# FAL6567.net
KiCad netlist of a schematic drawn in EAGLE
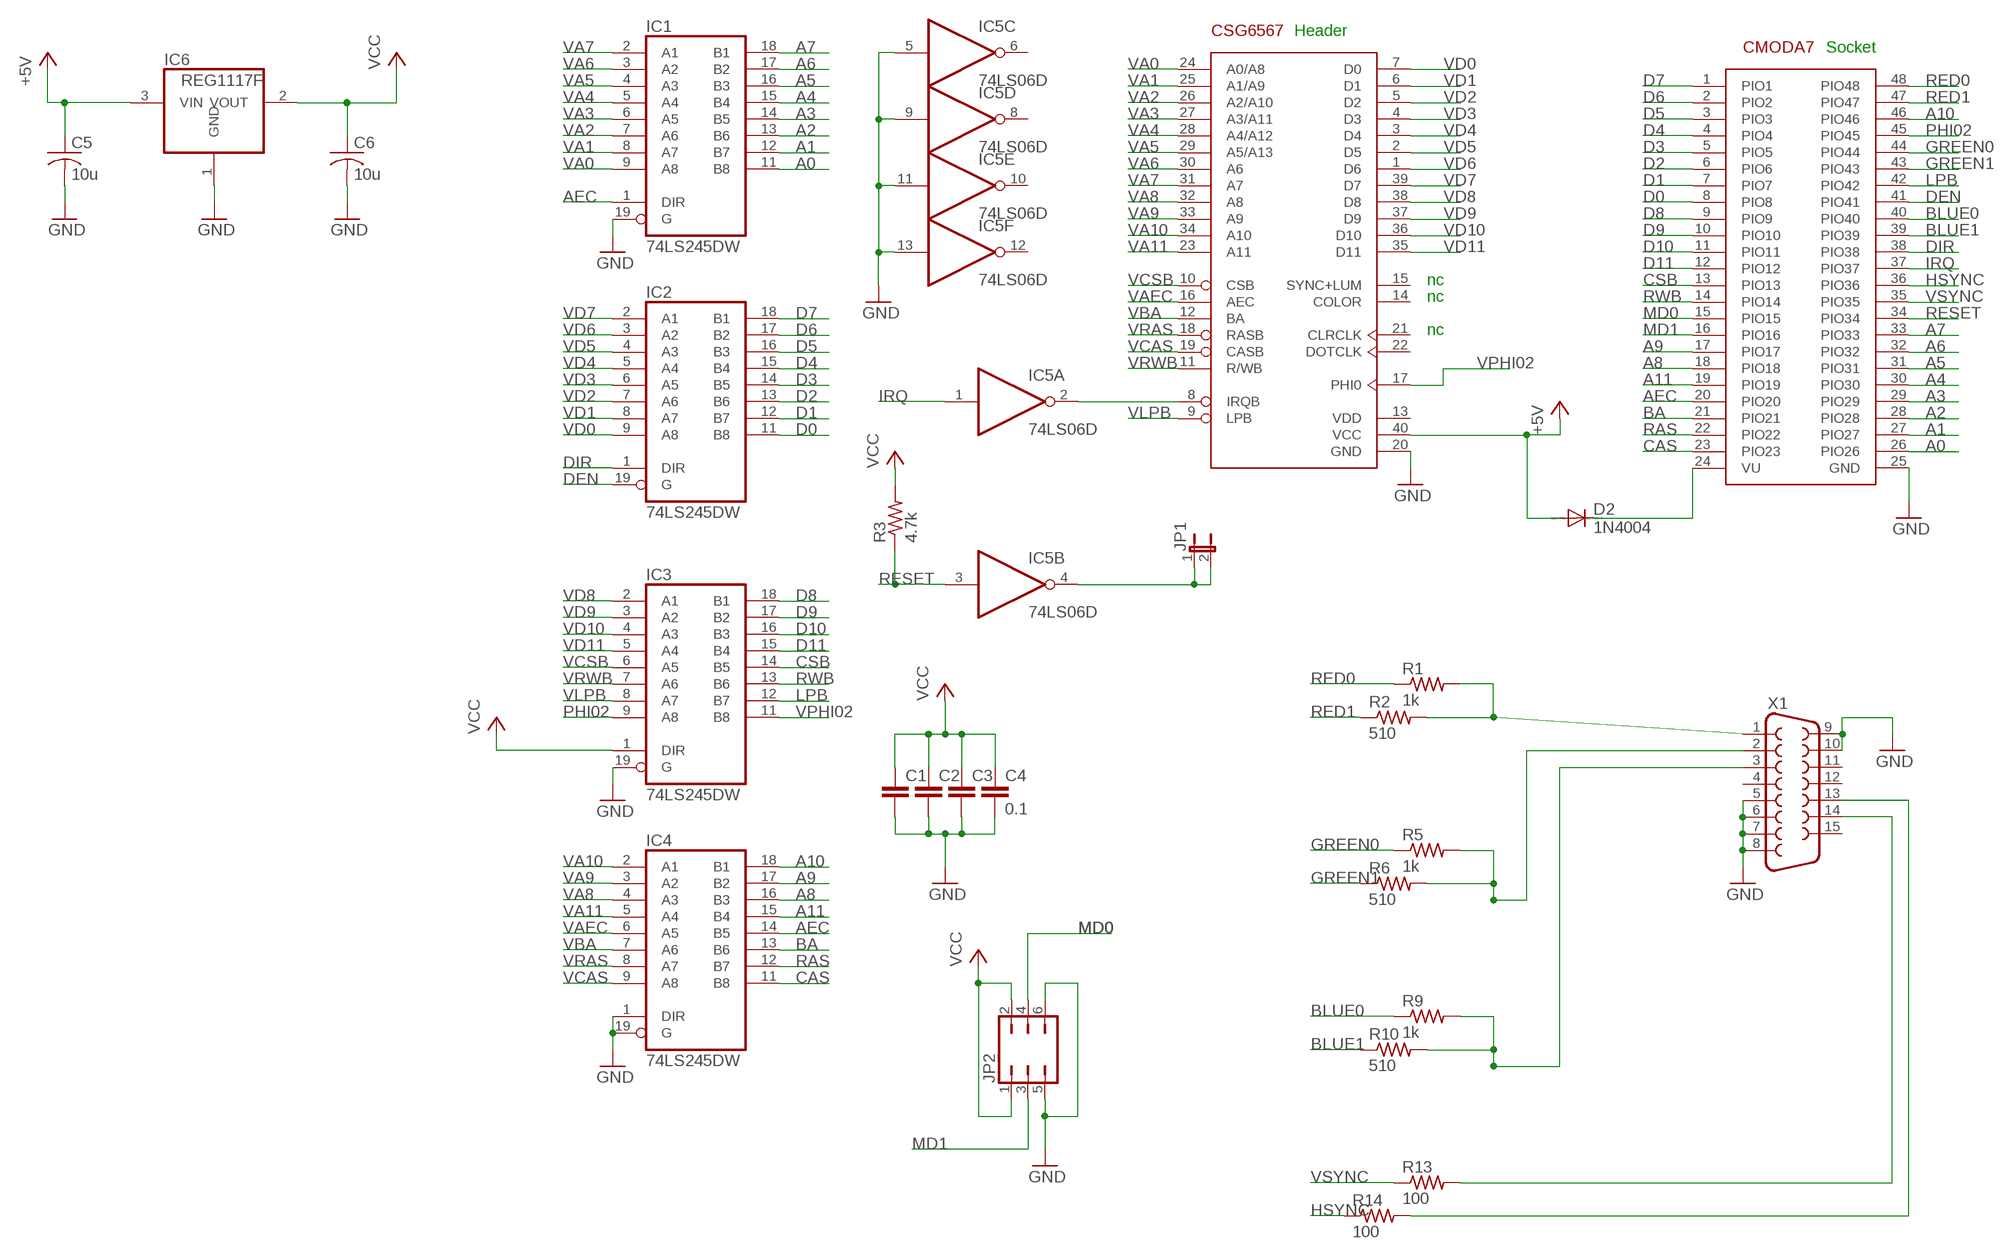
[diagram p0: schematic, sheet 1]

(export (version "E")
  (design (tool "Eeschema 10.0.6"))
  (components
    (comp (ref "C1")
      (value "C-EU050-024X044")
      (footprint "eagle-import:C050-024X044")
      (libsource (lib "eagle-import") (part "C-EU050-024X044"))
    )
    (comp (ref "C2")
      (value "C-EU050-024X044")
      (footprint "eagle-import:C050-024X044")
      (libsource (lib "eagle-import") (part "C-EU050-024X044"))
    )
    (comp (ref "C3")
      (value "C-EU050-024X044")
      (footprint "eagle-import:C050-024X044")
      (libsource (lib "eagle-import") (part "C-EU050-024X044"))
    )
    (comp (ref "C4")
      (value "0.1")
      (footprint "eagle-import:C050-024X044")
      (libsource (lib "eagle-import") (part "C-EU050-024X044"))
    )
    (comp (ref "C5")
      (value "10u")
      (footprint "eagle-import:C1206")
      (libsource (lib "eagle-import") (part "C-USC1206"))
    )
    (comp (ref "C6")
      (value "10u")
      (footprint "eagle-import:C1206")
      (libsource (lib "eagle-import") (part "C-USC1206"))
    )
    (comp (ref "D2")
      (value "1N4004")
      (footprint "eagle-import:DO41-10")
      (libsource (lib "eagle-import") (part "1N4004"))
    )
    (comp (ref "IC1")
      (value "74LS245DW")
      (footprint "eagle-import:SO20W")
      (libsource (lib "eagle-import") (part "74245DWLS"))
    )
    (comp (ref "IC2")
      (value "74LS245DW")
      (footprint "eagle-import:SO20W")
      (libsource (lib "eagle-import") (part "74245DWLS"))
    )
    (comp (ref "IC3")
      (value "74LS245DW")
      (footprint "eagle-import:SO20W")
      (libsource (lib "eagle-import") (part "74245DWLS"))
    )
    (comp (ref "IC4")
      (value "74LS245DW")
      (footprint "eagle-import:SO20W")
      (libsource (lib "eagle-import") (part "74245DWLS"))
    )
    (comp (ref "IC5")
      (value "74LS06D")
      (footprint "eagle-import:SO14")
      (libsource (lib "eagle-import") (part "7406DLS"))
    )
    (comp (ref "IC6")
      (value "REG1117F")
      (footprint "eagle-import:DD-3")
      (fields (field (name "MF") "TEXAS INSTRUMENTS") (field (name "MPN") "REG1117FAKTTT"))
      (libsource (lib "eagle-import") (part "REG1117F"))
    )
    (comp (ref "JP1")
      (value "JP1E")
      (footprint "eagle-import:JP1")
      (libsource (lib "eagle-import") (part "JP1E"))
    )
    (comp (ref "JP2")
      (value "JP3Q")
      (footprint "eagle-import:JP3Q")
      (libsource (lib "eagle-import") (part "JP3Q"))
    )
    (comp (ref "R1")
      (value "1k")
      (footprint "eagle-import:0204_7")
      (libsource (lib "eagle-import") (part "R-US_0204/7"))
    )
    (comp (ref "R2")
      (value "510")
      (footprint "eagle-import:0204_7")
      (libsource (lib "eagle-import") (part "R-US_0204/7"))
    )
    (comp (ref "R3")
      (value "4.7k")
      (footprint "eagle-import:0204_7")
      (libsource (lib "eagle-import") (part "R-US_0204/7"))
    )
    (comp (ref "R5")
      (value "1k")
      (footprint "eagle-import:0204_7")
      (libsource (lib "eagle-import") (part "R-US_0204/7"))
    )
    (comp (ref "R6")
      (value "510")
      (footprint "eagle-import:0204_7")
      (libsource (lib "eagle-import") (part "R-US_0204/7"))
    )
    (comp (ref "R9")
      (value "1k")
      (footprint "eagle-import:0204_7")
      (libsource (lib "eagle-import") (part "R-US_0204/7"))
    )
    (comp (ref "R10")
      (value "510")
      (footprint "eagle-import:0204_7")
      (libsource (lib "eagle-import") (part "R-US_0204/7"))
    )
    (comp (ref "R13")
      (value "100")
      (footprint "eagle-import:0204_7")
      (libsource (lib "eagle-import") (part "R-US_0204/7"))
    )
    (comp (ref "R14")
      (value "100")
      (footprint "eagle-import:0204_7")
      (libsource (lib "eagle-import") (part "R-US_0204/7"))
    )
    (comp (ref "U$1")
      (value "CSG6567")
      (footprint "eagle-import:DIP-40")
      (libsource (lib "eagle-import") (part "CSG6567"))
    )
    (comp (ref "U$2")
      (value "CMODA7")
      (footprint "eagle-import:DIL48")
      (libsource (lib "eagle-import") (part "CMODA7"))
    )
    (comp (ref "X1")
      (value "F15HDV")
      (footprint "eagle-import:HDF15V")
      (libsource (lib "eagle-import") (part "F15HDV"))
    )
  )
  (nets
    (net (code "1") (name "+5V") (class "Default")
      (node (ref "C5") (pin "1") (pinfunction "1_1") (pintype "passive"))
      (node (ref "D2") (pin "A") (pinfunction "A_A") (pintype "passive"))
      (node (ref "IC6") (pin "3") (pinfunction "VIN_3") (pintype "input"))
      (node (ref "U$1") (pin "40") (pinfunction "VCC_40") (pintype "power_in"))
    )
    (net (code "2") (name "/A0") (class "Default")
      (node (ref "IC1") (pin "11") (pinfunction "B8_11") (pintype "bidirectional"))
      (node (ref "U$2") (pin "26") (pinfunction "PIO26_26") (pintype "bidirectional"))
    )
    (net (code "3") (name "/A1") (class "Default")
      (node (ref "IC1") (pin "12") (pinfunction "B7_12") (pintype "bidirectional"))
      (node (ref "U$2") (pin "27") (pinfunction "PIO27_27") (pintype "bidirectional"))
    )
    (net (code "4") (name "/A2") (class "Default")
      (node (ref "IC1") (pin "13") (pinfunction "B6_13") (pintype "bidirectional"))
      (node (ref "U$2") (pin "28") (pinfunction "PIO28_28") (pintype "bidirectional"))
    )
    (net (code "5") (name "/A3") (class "Default")
      (node (ref "IC1") (pin "14") (pinfunction "B5_14") (pintype "bidirectional"))
      (node (ref "U$2") (pin "29") (pinfunction "PIO29_29") (pintype "bidirectional"))
    )
    (net (code "6") (name "/A4") (class "Default")
      (node (ref "IC1") (pin "15") (pinfunction "B4_15") (pintype "bidirectional"))
      (node (ref "U$2") (pin "30") (pinfunction "PIO30_30") (pintype "bidirectional"))
    )
    (net (code "7") (name "/A5") (class "Default")
      (node (ref "IC1") (pin "16") (pinfunction "B3_16") (pintype "bidirectional"))
      (node (ref "U$2") (pin "31") (pinfunction "PIO31_31") (pintype "bidirectional"))
    )
    (net (code "8") (name "/A6") (class "Default")
      (node (ref "IC1") (pin "17") (pinfunction "B2_17") (pintype "bidirectional"))
      (node (ref "U$2") (pin "32") (pinfunction "PIO32_32") (pintype "bidirectional"))
    )
    (net (code "9") (name "/A7") (class "Default")
      (node (ref "IC1") (pin "18") (pinfunction "B1_18") (pintype "bidirectional"))
      (node (ref "U$2") (pin "33") (pinfunction "PIO33_33") (pintype "bidirectional"))
    )
    (net (code "10") (name "/A8") (class "Default")
      (node (ref "IC4") (pin "16") (pinfunction "B3_16") (pintype "bidirectional"))
      (node (ref "U$2") (pin "18") (pinfunction "PIO18_18") (pintype "bidirectional"))
    )
    (net (code "11") (name "/A9") (class "Default")
      (node (ref "IC4") (pin "17") (pinfunction "B2_17") (pintype "bidirectional"))
      (node (ref "U$2") (pin "17") (pinfunction "PIO17_17") (pintype "bidirectional"))
    )
    (net (code "12") (name "/A10") (class "Default")
      (node (ref "IC4") (pin "18") (pinfunction "B1_18") (pintype "bidirectional"))
      (node (ref "U$2") (pin "46") (pinfunction "PIO46_46") (pintype "bidirectional"))
    )
    (net (code "13") (name "/A11") (class "Default")
      (node (ref "IC4") (pin "15") (pinfunction "B4_15") (pintype "bidirectional"))
      (node (ref "U$2") (pin "19") (pinfunction "PIO19_19") (pintype "bidirectional"))
    )
    (net (code "14") (name "/AEC") (class "Default")
      (node (ref "IC1") (pin "1") (pinfunction "DIR_1") (pintype "input"))
      (node (ref "IC4") (pin "14") (pinfunction "B5_14") (pintype "bidirectional"))
      (node (ref "U$2") (pin "20") (pinfunction "PIO20_20") (pintype "bidirectional"))
    )
    (net (code "15") (name "/BA") (class "Default")
      (node (ref "IC4") (pin "13") (pinfunction "B6_13") (pintype "bidirectional"))
      (node (ref "U$2") (pin "21") (pinfunction "PIO21_21") (pintype "bidirectional"))
    )
    (net (code "16") (name "/BLUE0") (class "Default")
      (node (ref "R9") (pin "1") (pinfunction "1_1") (pintype "passive"))
      (node (ref "U$2") (pin "40") (pinfunction "PIO40_40") (pintype "bidirectional"))
    )
    (net (code "17") (name "/BLUE1") (class "Default")
      (node (ref "R10") (pin "1") (pinfunction "1_1") (pintype "passive"))
      (node (ref "U$2") (pin "39") (pinfunction "PIO39_39") (pintype "bidirectional"))
    )
    (net (code "18") (name "/CAS") (class "Default")
      (node (ref "IC4") (pin "11") (pinfunction "B8_11") (pintype "bidirectional"))
      (node (ref "U$2") (pin "23") (pinfunction "PIO23_23") (pintype "bidirectional"))
    )
    (net (code "19") (name "/CSB") (class "Default")
      (node (ref "IC3") (pin "14") (pinfunction "B5_14") (pintype "bidirectional"))
      (node (ref "U$2") (pin "13") (pinfunction "PIO13_13") (pintype "bidirectional"))
    )
    (net (code "20") (name "/D0") (class "Default")
      (node (ref "IC2") (pin "11") (pinfunction "B8_11") (pintype "bidirectional"))
      (node (ref "U$2") (pin "8") (pinfunction "PIO8_8") (pintype "bidirectional"))
    )
    (net (code "21") (name "/D1") (class "Default")
      (node (ref "IC2") (pin "12") (pinfunction "B7_12") (pintype "bidirectional"))
      (node (ref "U$2") (pin "7") (pinfunction "PIO7_7") (pintype "bidirectional"))
    )
    (net (code "22") (name "/D2") (class "Default")
      (node (ref "IC2") (pin "13") (pinfunction "B6_13") (pintype "bidirectional"))
      (node (ref "U$2") (pin "6") (pinfunction "PIO6_6") (pintype "bidirectional"))
    )
    (net (code "23") (name "/D3") (class "Default")
      (node (ref "IC2") (pin "14") (pinfunction "B5_14") (pintype "bidirectional"))
      (node (ref "U$2") (pin "5") (pinfunction "PIO5_5") (pintype "bidirectional"))
    )
    (net (code "24") (name "/D4") (class "Default")
      (node (ref "IC2") (pin "15") (pinfunction "B4_15") (pintype "bidirectional"))
      (node (ref "U$2") (pin "4") (pinfunction "PIO4_4") (pintype "bidirectional"))
    )
    (net (code "25") (name "/D5") (class "Default")
      (node (ref "IC2") (pin "16") (pinfunction "B3_16") (pintype "bidirectional"))
      (node (ref "U$2") (pin "3") (pinfunction "PIO3_3") (pintype "bidirectional"))
    )
    (net (code "26") (name "/D6") (class "Default")
      (node (ref "IC2") (pin "17") (pinfunction "B2_17") (pintype "bidirectional"))
      (node (ref "U$2") (pin "2") (pinfunction "PIO2_2") (pintype "bidirectional"))
    )
    (net (code "27") (name "/D7") (class "Default")
      (node (ref "IC2") (pin "18") (pinfunction "B1_18") (pintype "bidirectional"))
      (node (ref "U$2") (pin "1") (pinfunction "PIO1_1") (pintype "bidirectional"))
    )
    (net (code "28") (name "/D8") (class "Default")
      (node (ref "IC3") (pin "18") (pinfunction "B1_18") (pintype "bidirectional"))
      (node (ref "U$2") (pin "9") (pinfunction "PIO9_9") (pintype "bidirectional"))
    )
    (net (code "29") (name "/D9") (class "Default")
      (node (ref "IC3") (pin "17") (pinfunction "B2_17") (pintype "bidirectional"))
      (node (ref "U$2") (pin "10") (pinfunction "PIO10_10") (pintype "bidirectional"))
    )
    (net (code "30") (name "/D10") (class "Default")
      (node (ref "IC3") (pin "16") (pinfunction "B3_16") (pintype "bidirectional"))
      (node (ref "U$2") (pin "11") (pinfunction "PIO11_11") (pintype "bidirectional"))
    )
    (net (code "31") (name "/D11") (class "Default")
      (node (ref "IC3") (pin "15") (pinfunction "B4_15") (pintype "bidirectional"))
      (node (ref "U$2") (pin "12") (pinfunction "PIO12_12") (pintype "bidirectional"))
    )
    (net (code "32") (name "/DEN") (class "Default")
      (node (ref "IC2") (pin "19") (pinfunction "G_19") (pintype "input"))
      (node (ref "U$2") (pin "41") (pinfunction "PIO41_41") (pintype "bidirectional"))
    )
    (net (code "33") (name "/DIR") (class "Default")
      (node (ref "IC2") (pin "1") (pinfunction "DIR_1") (pintype "input"))
      (node (ref "U$2") (pin "38") (pinfunction "PIO38_38") (pintype "bidirectional"))
    )
    (net (code "34") (name "/GREEN0") (class "Default")
      (node (ref "R5") (pin "1") (pinfunction "1_1") (pintype "passive"))
      (node (ref "U$2") (pin "44") (pinfunction "PIO44_44") (pintype "bidirectional"))
    )
    (net (code "35") (name "/GREEN1") (class "Default")
      (node (ref "R6") (pin "1") (pinfunction "1_1") (pintype "passive"))
      (node (ref "U$2") (pin "43") (pinfunction "PIO43_43") (pintype "bidirectional"))
    )
    (net (code "36") (name "/HSYNC") (class "Default")
      (node (ref "R14") (pin "1") (pinfunction "1_1") (pintype "passive"))
      (node (ref "U$2") (pin "36") (pinfunction "PIO36_36") (pintype "bidirectional"))
    )
    (net (code "37") (name "/IRQ") (class "Default")
      (node (ref "IC5") (pin "1") (pinfunction "I_1") (pintype "input"))
      (node (ref "U$2") (pin "37") (pinfunction "PIO37_37") (pintype "bidirectional"))
    )
    (net (code "38") (name "/LPB") (class "Default")
      (node (ref "IC3") (pin "12") (pinfunction "B7_12") (pintype "bidirectional"))
      (node (ref "U$2") (pin "42") (pinfunction "PIO42_42") (pintype "bidirectional"))
    )
    (net (code "39") (name "/MD0") (class "Default")
      (node (ref "JP2") (pin "4") (pinfunction "4_4") (pintype "passive"))
      (node (ref "U$2") (pin "15") (pinfunction "PIO15_15") (pintype "bidirectional"))
    )
    (net (code "40") (name "/MD1") (class "Default")
      (node (ref "JP2") (pin "3") (pinfunction "3_3") (pintype "passive"))
      (node (ref "U$2") (pin "16") (pinfunction "PIO16_16") (pintype "bidirectional"))
    )
    (net (code "41") (name "/PHI02") (class "Default")
      (node (ref "IC3") (pin "9") (pinfunction "A8_9") (pintype "bidirectional"))
      (node (ref "U$2") (pin "45") (pinfunction "PIO45_45") (pintype "bidirectional"))
    )
    (net (code "42") (name "/RAS") (class "Default")
      (node (ref "IC4") (pin "12") (pinfunction "B7_12") (pintype "bidirectional"))
      (node (ref "U$2") (pin "22") (pinfunction "PIO22_22") (pintype "bidirectional"))
    )
    (net (code "43") (name "/RED0") (class "Default")
      (node (ref "R1") (pin "1") (pinfunction "1_1") (pintype "passive"))
      (node (ref "U$2") (pin "48") (pinfunction "PIO48_48") (pintype "bidirectional"))
    )
    (net (code "44") (name "/RED1") (class "Default")
      (node (ref "R2") (pin "1") (pinfunction "1_1") (pintype "passive"))
      (node (ref "U$2") (pin "47") (pinfunction "PIO47_47") (pintype "bidirectional"))
    )
    (net (code "45") (name "/RESET") (class "Default")
      (node (ref "IC5") (pin "3") (pinfunction "I_3") (pintype "input"))
      (node (ref "R3") (pin "1") (pinfunction "1_1") (pintype "passive"))
      (node (ref "U$2") (pin "34") (pinfunction "PIO34_34") (pintype "bidirectional"))
    )
    (net (code "46") (name "/RWB") (class "Default")
      (node (ref "IC3") (pin "13") (pinfunction "B6_13") (pintype "bidirectional"))
      (node (ref "U$2") (pin "14") (pinfunction "PIO14_14") (pintype "bidirectional"))
    )
    (net (code "47") (name "/VA0") (class "Default")
      (node (ref "IC1") (pin "9") (pinfunction "A8_9") (pintype "bidirectional"))
      (node (ref "U$1") (pin "24") (pinfunction "A0/A8_24") (pintype "bidirectional"))
    )
    (net (code "48") (name "/VA1") (class "Default")
      (node (ref "IC1") (pin "8") (pinfunction "A7_8") (pintype "bidirectional"))
      (node (ref "U$1") (pin "25") (pinfunction "A1/A9_25") (pintype "bidirectional"))
    )
    (net (code "49") (name "/VA2") (class "Default")
      (node (ref "IC1") (pin "7") (pinfunction "A6_7") (pintype "bidirectional"))
      (node (ref "U$1") (pin "26") (pinfunction "A2/A10_26") (pintype "bidirectional"))
    )
    (net (code "50") (name "/VA3") (class "Default")
      (node (ref "IC1") (pin "6") (pinfunction "A5_6") (pintype "bidirectional"))
      (node (ref "U$1") (pin "27") (pinfunction "A3/A11_27") (pintype "bidirectional"))
    )
    (net (code "51") (name "/VA4") (class "Default")
      (node (ref "IC1") (pin "5") (pinfunction "A4_5") (pintype "bidirectional"))
      (node (ref "U$1") (pin "28") (pinfunction "A4/A12_28") (pintype "bidirectional"))
    )
    (net (code "52") (name "/VA5") (class "Default")
      (node (ref "IC1") (pin "4") (pinfunction "A3_4") (pintype "bidirectional"))
      (node (ref "U$1") (pin "29") (pinfunction "A5/A13_29") (pintype "bidirectional"))
    )
    (net (code "53") (name "/VA6") (class "Default")
      (node (ref "IC1") (pin "3") (pinfunction "A2_3") (pintype "bidirectional"))
      (node (ref "U$1") (pin "30") (pinfunction "A6_30") (pintype "bidirectional"))
    )
    (net (code "54") (name "/VA7") (class "Default")
      (node (ref "IC1") (pin "2") (pinfunction "A1_2") (pintype "bidirectional"))
      (node (ref "U$1") (pin "31") (pinfunction "A7_31") (pintype "bidirectional"))
    )
    (net (code "55") (name "/VA8") (class "Default")
      (node (ref "IC4") (pin "4") (pinfunction "A3_4") (pintype "bidirectional"))
      (node (ref "U$1") (pin "32") (pinfunction "A8_32") (pintype "output"))
    )
    (net (code "56") (name "/VA9") (class "Default")
      (node (ref "IC4") (pin "3") (pinfunction "A2_3") (pintype "bidirectional"))
      (node (ref "U$1") (pin "33") (pinfunction "A9_33") (pintype "output"))
    )
    (net (code "57") (name "/VA10") (class "Default")
      (node (ref "IC4") (pin "2") (pinfunction "A1_2") (pintype "bidirectional"))
      (node (ref "U$1") (pin "34") (pinfunction "A10_34") (pintype "output"))
    )
    (net (code "58") (name "/VA11") (class "Default")
      (node (ref "IC4") (pin "5") (pinfunction "A4_5") (pintype "bidirectional"))
      (node (ref "U$1") (pin "23") (pinfunction "A11_23") (pintype "output"))
    )
    (net (code "59") (name "/VAEC") (class "Default")
      (node (ref "IC4") (pin "6") (pinfunction "A5_6") (pintype "bidirectional"))
      (node (ref "U$1") (pin "16") (pinfunction "AEC_16") (pintype "output"))
    )
    (net (code "60") (name "/VBA") (class "Default")
      (node (ref "IC4") (pin "7") (pinfunction "A6_7") (pintype "bidirectional"))
      (node (ref "U$1") (pin "12") (pinfunction "BA_12") (pintype "output"))
    )
    (net (code "61") (name "/VCAS") (class "Default")
      (node (ref "IC4") (pin "9") (pinfunction "A8_9") (pintype "bidirectional"))
      (node (ref "U$1") (pin "19") (pinfunction "CASB_19") (pintype "output"))
    )
    (net (code "62") (name "/VCSB") (class "Default")
      (node (ref "IC3") (pin "6") (pinfunction "A5_6") (pintype "bidirectional"))
      (node (ref "U$1") (pin "10") (pinfunction "CSB_10") (pintype "input"))
    )
    (net (code "63") (name "/VD0") (class "Default")
      (node (ref "IC2") (pin "9") (pinfunction "A8_9") (pintype "bidirectional"))
      (node (ref "U$1") (pin "7") (pinfunction "D0_7") (pintype "bidirectional"))
    )
    (net (code "64") (name "/VD1") (class "Default")
      (node (ref "IC2") (pin "8") (pinfunction "A7_8") (pintype "bidirectional"))
      (node (ref "U$1") (pin "6") (pinfunction "D1_6") (pintype "bidirectional"))
    )
    (net (code "65") (name "/VD2") (class "Default")
      (node (ref "IC2") (pin "7") (pinfunction "A6_7") (pintype "bidirectional"))
      (node (ref "U$1") (pin "5") (pinfunction "D2_5") (pintype "bidirectional"))
    )
    (net (code "66") (name "/VD3") (class "Default")
      (node (ref "IC2") (pin "6") (pinfunction "A5_6") (pintype "bidirectional"))
      (node (ref "U$1") (pin "4") (pinfunction "D3_4") (pintype "bidirectional"))
    )
    (net (code "67") (name "/VD4") (class "Default")
      (node (ref "IC2") (pin "5") (pinfunction "A4_5") (pintype "bidirectional"))
      (node (ref "U$1") (pin "3") (pinfunction "D4_3") (pintype "bidirectional"))
    )
    (net (code "68") (name "/VD5") (class "Default")
      (node (ref "IC2") (pin "4") (pinfunction "A3_4") (pintype "bidirectional"))
      (node (ref "U$1") (pin "2") (pinfunction "D5_2") (pintype "bidirectional"))
    )
    (net (code "69") (name "/VD6") (class "Default")
      (node (ref "IC2") (pin "3") (pinfunction "A2_3") (pintype "bidirectional"))
      (node (ref "U$1") (pin "1") (pinfunction "D6_1") (pintype "bidirectional"))
    )
    (net (code "70") (name "/VD7") (class "Default")
      (node (ref "IC2") (pin "2") (pinfunction "A1_2") (pintype "bidirectional"))
      (node (ref "U$1") (pin "39") (pinfunction "D7_39") (pintype "bidirectional"))
    )
    (net (code "71") (name "/VD8") (class "Default")
      (node (ref "IC3") (pin "2") (pinfunction "A1_2") (pintype "bidirectional"))
      (node (ref "U$1") (pin "38") (pinfunction "D8_38") (pintype "input"))
    )
    (net (code "72") (name "/VD9") (class "Default")
      (node (ref "IC3") (pin "3") (pinfunction "A2_3") (pintype "bidirectional"))
      (node (ref "U$1") (pin "37") (pinfunction "D9_37") (pintype "input"))
    )
    (net (code "73") (name "/VD10") (class "Default")
      (node (ref "IC3") (pin "4") (pinfunction "A3_4") (pintype "bidirectional"))
      (node (ref "U$1") (pin "36") (pinfunction "D10_36") (pintype "input"))
    )
    (net (code "74") (name "/VD11") (class "Default")
      (node (ref "IC3") (pin "5") (pinfunction "A4_5") (pintype "bidirectional"))
      (node (ref "U$1") (pin "35") (pinfunction "D11_35") (pintype "input"))
    )
    (net (code "75") (name "/VDD") (class "Default")
      (node (ref "U$1") (pin "13") (pinfunction "VDD_13") (pintype "power_in"))
    )
    (net (code "76") (name "/VLPB") (class "Default")
      (node (ref "IC3") (pin "8") (pinfunction "A7_8") (pintype "bidirectional"))
      (node (ref "U$1") (pin "9") (pinfunction "LPB_9") (pintype "input"))
    )
    (net (code "77") (name "/VPHI02") (class "Default")
      (node (ref "IC3") (pin "11") (pinfunction "B8_11") (pintype "bidirectional"))
      (node (ref "U$1") (pin "17") (pinfunction "PHI0_17") (pintype "output"))
    )
    (net (code "78") (name "/VRAS") (class "Default")
      (node (ref "IC4") (pin "8") (pinfunction "A7_8") (pintype "bidirectional"))
      (node (ref "U$1") (pin "18") (pinfunction "RASB_18") (pintype "output"))
    )
    (net (code "79") (name "/VRWB") (class "Default")
      (node (ref "IC3") (pin "7") (pinfunction "A6_7") (pintype "bidirectional"))
      (node (ref "U$1") (pin "11") (pinfunction "R/WB_11") (pintype "input"))
    )
    (net (code "80") (name "/VSYNC") (class "Default")
      (node (ref "R13") (pin "1") (pinfunction "1_1") (pintype "passive"))
      (node (ref "U$2") (pin "35") (pinfunction "PIO35_35") (pintype "bidirectional"))
    )
    (net (code "81") (name "GND") (class "Default")
      (node (ref "C1") (pin "2") (pinfunction "2_2") (pintype "passive"))
      (node (ref "C2") (pin "2") (pinfunction "2_2") (pintype "passive"))
      (node (ref "C3") (pin "2") (pinfunction "2_2") (pintype "passive"))
      (node (ref "C4") (pin "2") (pinfunction "2_2") (pintype "passive"))
      (node (ref "C5") (pin "2") (pinfunction "2_2") (pintype "passive"))
      (node (ref "C6") (pin "2") (pinfunction "2_2") (pintype "passive"))
      (node (ref "IC1") (pin "19") (pinfunction "G_19") (pintype "input"))
      (node (ref "IC3") (pin "19") (pinfunction "G_19") (pintype "input"))
      (node (ref "IC4") (pin "1") (pinfunction "DIR_1") (pintype "input"))
      (node (ref "IC4") (pin "19") (pinfunction "G_19") (pintype "input"))
      (node (ref "IC5") (pin "11") (pinfunction "I_11") (pintype "input"))
      (node (ref "IC5") (pin "13") (pinfunction "I_13") (pintype "input"))
      (node (ref "IC5") (pin "5") (pinfunction "I_5") (pintype "input"))
      (node (ref "IC5") (pin "9") (pinfunction "I_9") (pintype "input"))
      (node (ref "IC6") (pin "1") (pinfunction "GND_1") (pintype "power_in"))
      (node (ref "JP2") (pin "5") (pinfunction "5_5") (pintype "passive"))
      (node (ref "JP2") (pin "6") (pinfunction "6_6") (pintype "passive"))
      (node (ref "U$1") (pin "20") (pinfunction "GND_20") (pintype "power_in"))
      (node (ref "U$2") (pin "25") (pinfunction "GND_25") (pintype "power_in"))
      (node (ref "X1") (pin "10") (pinfunction "10_10") (pintype "passive"))
      (node (ref "X1") (pin "5") (pinfunction "5_5") (pintype "passive"))
      (node (ref "X1") (pin "6") (pinfunction "6_6") (pintype "passive"))
      (node (ref "X1") (pin "7") (pinfunction "7_7") (pintype "passive"))
      (node (ref "X1") (pin "8") (pinfunction "8_8") (pintype "passive"))
      (node (ref "X1") (pin "9") (pinfunction "9_9") (pintype "passive"))
    )
    (net (code "82") (name "Net-(IC5A-O)") (class "Default")
      (node (ref "IC5") (pin "2") (pinfunction "O_2") (pintype "open_collector"))
      (node (ref "U$1") (pin "8") (pinfunction "IRQB_8") (pintype "open_collector"))
    )
    (net (code "83") (name "Net-(IC5B-O)") (class "Default")
      (node (ref "IC5") (pin "4") (pinfunction "O_4") (pintype "open_collector"))
      (node (ref "JP1") (pin "1") (pinfunction "1_1") (pintype "passive"))
      (node (ref "JP1") (pin "2") (pinfunction "2_2") (pintype "passive"))
    )
    (net (code "84") (name "Net-(R1-Pad2)") (class "Default")
      (node (ref "R1") (pin "2") (pinfunction "2_2") (pintype "passive"))
      (node (ref "R2") (pin "2") (pinfunction "2_2") (pintype "passive"))
      (node (ref "X1") (pin "1") (pinfunction "1_1") (pintype "passive"))
    )
    (net (code "85") (name "Net-(R5-Pad2)") (class "Default")
      (node (ref "R5") (pin "2") (pinfunction "2_2") (pintype "passive"))
      (node (ref "R6") (pin "2") (pinfunction "2_2") (pintype "passive"))
      (node (ref "X1") (pin "2") (pinfunction "2_2") (pintype "passive"))
    )
    (net (code "86") (name "Net-(R10-Pad2)") (class "Default")
      (node (ref "R10") (pin "2") (pinfunction "2_2") (pintype "passive"))
      (node (ref "R9") (pin "2") (pinfunction "2_2") (pintype "passive"))
      (node (ref "X1") (pin "3") (pinfunction "3_3") (pintype "passive"))
    )
    (net (code "87") (name "Net-(R13-Pad2)") (class "Default")
      (node (ref "R13") (pin "2") (pinfunction "2_2") (pintype "passive"))
      (node (ref "X1") (pin "14") (pinfunction "14_14") (pintype "passive"))
    )
    (net (code "88") (name "Net-(R14-Pad2)") (class "Default")
      (node (ref "R14") (pin "2") (pinfunction "2_2") (pintype "passive"))
      (node (ref "X1") (pin "13") (pinfunction "13_13") (pintype "passive"))
    )
    (net (code "89") (name "Net-(U$2-VU)") (class "Default")
      (node (ref "D2") (pin "C") (pinfunction "C_C") (pintype "passive"))
      (node (ref "U$2") (pin "24") (pinfunction "VU_24") (pintype "power_in"))
    )
    (net (code "90") (name "VCC") (class "Default")
      (node (ref "C1") (pin "1") (pinfunction "1_1") (pintype "passive"))
      (node (ref "C2") (pin "1") (pinfunction "1_1") (pintype "passive"))
      (node (ref "C3") (pin "1") (pinfunction "1_1") (pintype "passive"))
      (node (ref "C4") (pin "1") (pinfunction "1_1") (pintype "passive"))
      (node (ref "C6") (pin "1") (pinfunction "1_1") (pintype "passive"))
      (node (ref "IC3") (pin "1") (pinfunction "DIR_1") (pintype "input"))
      (node (ref "IC6") (pin "2") (pinfunction "VOUT_2") (pintype "output"))
      (node (ref "JP2") (pin "1") (pinfunction "1_1") (pintype "passive"))
      (node (ref "JP2") (pin "2") (pinfunction "2_2") (pintype "passive"))
      (node (ref "R3") (pin "2") (pinfunction "2_2") (pintype "passive"))
    )
    (net (code "91") (name "unconnected-(IC5C-O-Pad6)") (class "Default")
      (node (ref "IC5") (pin "6") (pinfunction "O_6") (pintype "open_collector"))
    )
    (net (code "92") (name "unconnected-(IC5D-O-Pad8)") (class "Default")
      (node (ref "IC5") (pin "8") (pinfunction "O_8") (pintype "open_collector"))
    )
    (net (code "93") (name "unconnected-(IC5E-O-Pad10)") (class "Default")
      (node (ref "IC5") (pin "10") (pinfunction "O_10") (pintype "open_collector"))
    )
    (net (code "94") (name "unconnected-(IC5F-O-Pad12)") (class "Default")
      (node (ref "IC5") (pin "12") (pinfunction "O_12") (pintype "open_collector"))
    )
    (net (code "95") (name "unconnected-(U$1-CLRCLK-Pad21)") (class "Default")
      (node (ref "U$1") (pin "21") (pinfunction "CLRCLK_21") (pintype "input"))
    )
    (net (code "96") (name "unconnected-(U$1-COLOR-Pad14)") (class "Default")
      (node (ref "U$1") (pin "14") (pinfunction "COLOR_14") (pintype "output"))
    )
    (net (code "97") (name "unconnected-(U$1-DOTCLK-Pad22)") (class "Default")
      (node (ref "U$1") (pin "22") (pinfunction "DOTCLK_22") (pintype "input"))
    )
    (net (code "98") (name "unconnected-(U$1-SYNC+LUM-Pad15)") (class "Default")
      (node (ref "U$1") (pin "15") (pinfunction "SYNC+LUM_15") (pintype "output"))
    )
    (net (code "99") (name "unconnected-(X1-Pad4)") (class "Default")
      (node (ref "X1") (pin "4") (pinfunction "4_4") (pintype "passive"))
    )
    (net (code "100") (name "unconnected-(X1-Pad11)") (class "Default")
      (node (ref "X1") (pin "11") (pinfunction "11_11") (pintype "passive"))
    )
    (net (code "101") (name "unconnected-(X1-Pad12)") (class "Default")
      (node (ref "X1") (pin "12") (pinfunction "12_12") (pintype "passive"))
    )
    (net (code "102") (name "unconnected-(X1-Pad15)") (class "Default")
      (node (ref "X1") (pin "15") (pinfunction "15_15") (pintype "passive"))
    )
  )
)
